# Sheet2.net
KiCad netlist of a schematic drawn in Altium Designer
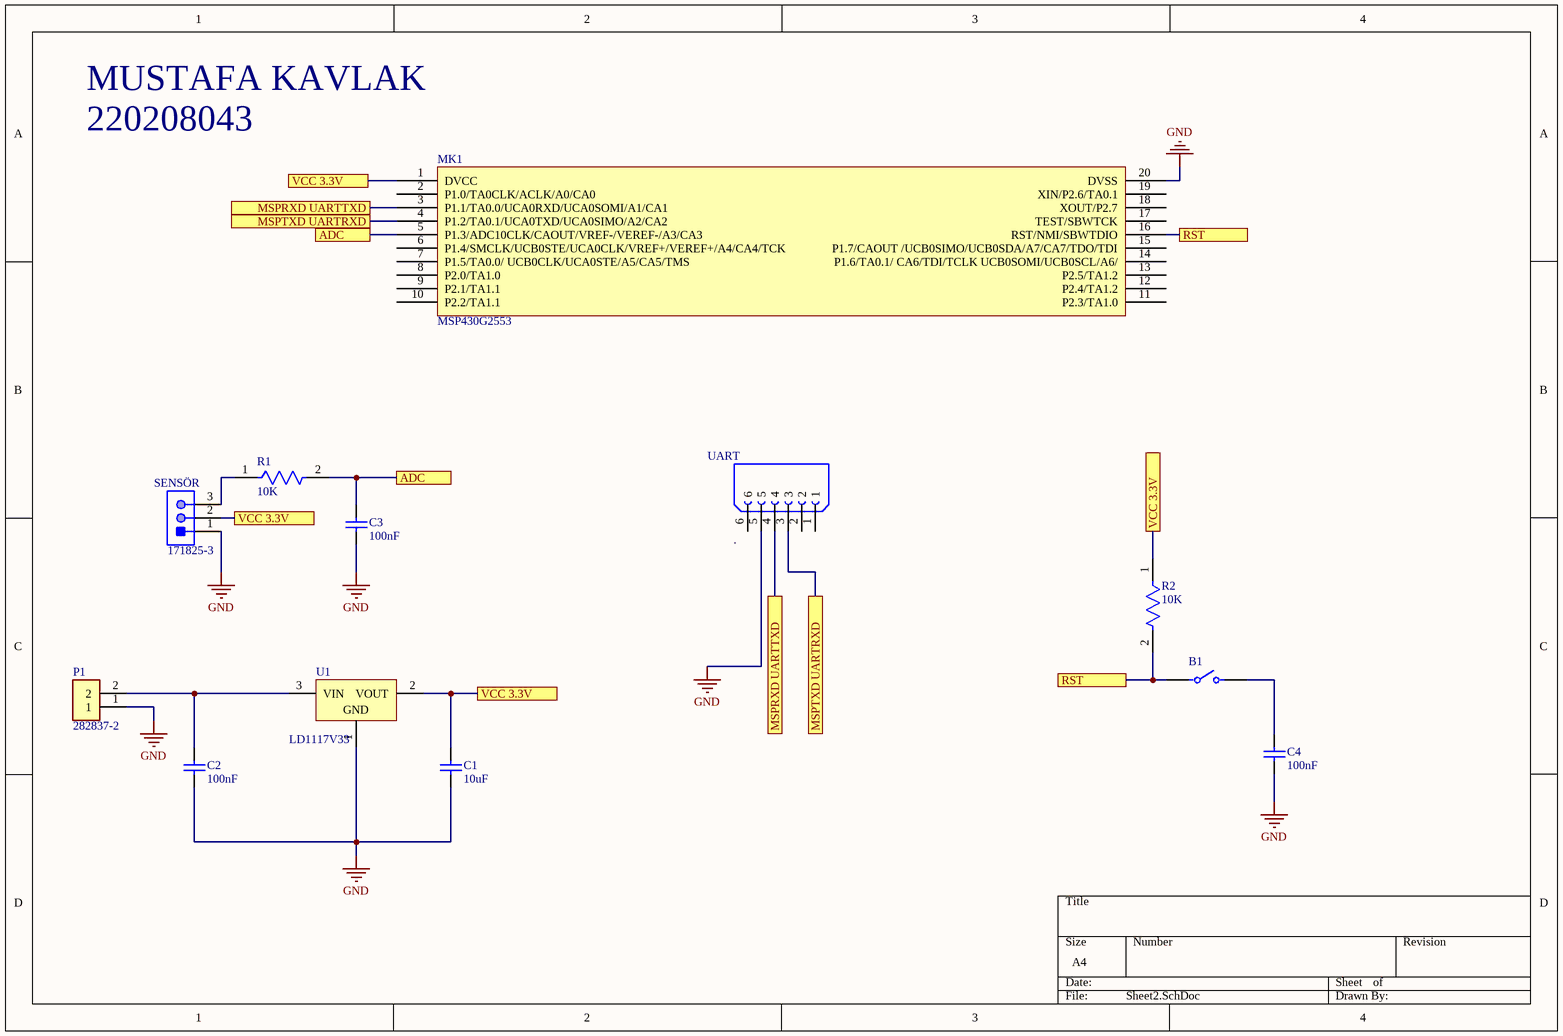
[diagram p0: Sheet2.SchDoc]

(export (version "E")
  (design (tool "Eeschema 10.0.6"))
  (components
    (comp (ref "B1")
      (value "1")
      (footprint "FP-147873-1-MFG")
      (description "SWITCH TACTILE SPST-NO 0.05A 24V")
      (fields
        (field (name "MANUFACTURER") "TE Connectivity")
        (field (name "MANUFACTURER PART NUMBER") "147873-1")
      )
      (libsource (lib "Altium Content Vault") (part "bb27bde45df87f1f469753f287ef5ae"))
    )
    (comp (ref "C1")
      (value "10uF")
      (footprint "CAPC1210(3225)100_M")
      (description "CAP 10nF 250V ±5% 1210 (3225 Metric) Thickness 1mm SMD")
      (fields (field (name "TOLERANCE") "Â±5%"))
      (libsource (lib "Altium Content Vault") (part "CAP"))
    )
    (comp (ref "C2")
      (value "100nF")
      (footprint "CAPC1210(3225)100_M")
      (description "CAP 10nF 250V ±5% 1210 (3225 Metric) Thickness 1mm SMD")
      (fields (field (name "TOLERANCE") "Â±5%"))
      (libsource (lib "Altium Content Vault") (part "CAP"))
    )
    (comp (ref "C3")
      (value "100nF")
      (footprint "CAPC1210(3225)100_M")
      (description "CAP 10nF 250V ±5% 1210 (3225 Metric) Thickness 1mm SMD")
      (fields (field (name "TOLERANCE") "Â±5%"))
      (libsource (lib "Altium Content Vault") (part "CAP"))
    )
    (comp (ref "C4")
      (value "100nF")
      (footprint "CAPC1210(3225)100_M")
      (description "CAP 10nF 250V ±5% 1210 (3225 Metric) Thickness 1mm SMD")
      (fields (field (name "TOLERANCE") "Â±5%"))
      (libsource (lib "Altium Content Vault") (part "CAP"))
    )
    (comp (ref "MK1")
      (value "MSP430G2553")
      (footprint "DIP20")
      (libsource (lib "Integrated_Library1") (part "MSP430G2553"))
    )
    (comp (ref "P1")
      (value "282837-2")
      (footprint "TE_282837-2")
      (fields (field (name "MF") "TE Connectivity"))
      (libsource (lib "282837-2") (part "282837-2"))
    )
    (comp (ref "R1")
      (value "10K")
      (footprint "FP-CRCW2512-e3-IPC_A")
      (description "RES Thick Film, 10kΩ, 5%, 1W, 200ppm/°C, 2512")
      (fields (field (name "TOLERANCE") "5%"))
      (libsource (lib "Altium Content Vault") (part "1029c3af85768c4190bb7ad29bc67b5"))
    )
    (comp (ref "R2")
      (value "10K")
      (footprint "FP-CRCW2512-e3-IPC_A")
      (description "RES Thick Film, 10kΩ, 5%, 1W, 200ppm/°C, 2512")
      (fields (field (name "TOLERANCE") "5%"))
      (libsource (lib "Altium Content Vault") (part "1029c3af85768c4190bb7ad29bc67b5"))
    )
    (comp (ref "SENSÖR")
      (value "171825-3")
      (footprint "TECO-171825-3_V")
      (fields (field (name "MANUFACTURER") "TE Connectivity"))
      (libsource (lib "Altium Content Vault") (part "CN-1P-M-R3"))
    )
    (comp (ref "U1")
      (value "LD1117V33")
      (footprint "TO220")
      (description "Fixed Low Drop Positive Voltage Regulator, 3.3V, 3-Pin TO-220")
      (libsource (lib "Altium Content Vault") (part "PM-REG-LD1117V-SIL3"))
    )
    (comp (ref "UART")
      (value ".")
      (footprint "PPTC061LFBNRC:SULLINS_PPTC061LFBN-RC")
      (fields
        (field (name "MF") "{'manufacturer': u'Sullins Connector Solutions'}")
        (field (name "MP") "PPTC061LFBN-RC")
      )
      (libsource (lib "*") (part "PPTC061LFBN-RC"))
    )
  )
  (nets
    (net (code "1") (name "/ADC") (class "Default")
      (node (ref "C3") (pin "2") (pinfunction "2_2") (pintype "passive"))
      (node (ref "MK1") (pin "5") (pinfunction "P1.3/ADC10CLK/CAOUT/VREF-/VEREF-/A3/CA3_5") (pintype "passive"))
      (node (ref "R1") (pin "2") (pinfunction "2_2") (pintype "passive"))
    )
    (net (code "2") (name "/MSPRXD UARTTXD") (class "Default")
      (node (ref "MK1") (pin "3") (pinfunction "P1.1/TA0.0/UCA0RXD/UCA0SOMI/A1/CA1_3") (pintype "passive"))
      (node (ref "UART") (pin "4") (pinfunction "4_4") (pintype "passive"))
    )
    (net (code "3") (name "/MSPTXD UARTRXD") (class "Default")
      (node (ref "MK1") (pin "4") (pinfunction "P1.2/TA0.1/UCA0TXD/UCA0SIMO/A2/CA2_4") (pintype "passive"))
      (node (ref "UART") (pin "3") (pinfunction "3_3") (pintype "passive"))
    )
    (net (code "4") (name "/RST") (class "Default")
      (node (ref "B1") (pin "1") (pinfunction "1_1") (pintype "passive"))
      (node (ref "MK1") (pin "16") (pinfunction "RST/NMI/SBWTDIO_16") (pintype "passive"))
      (node (ref "R2") (pin "2") (pinfunction "2_2") (pintype "passive"))
    )
    (net (code "5") (name "/VCC 3.3V") (class "Default")
      (node (ref "C1") (pin "2") (pinfunction "2_2") (pintype "passive"))
      (node (ref "MK1") (pin "1") (pinfunction "DVCC_1") (pintype "passive"))
      (node (ref "R2") (pin "1") (pinfunction "1_1") (pintype "passive"))
      (node (ref "SENSÖR") (pin "2") (pinfunction "2_2") (pintype "passive"))
      (node (ref "U1") (pin "2") (pinfunction "VOUT_2") (pintype "power_in"))
    )
    (net (code "6") (name "GND") (class "Default")
      (node (ref "C1") (pin "1") (pinfunction "1_1") (pintype "passive"))
      (node (ref "C2") (pin "1") (pinfunction "1_1") (pintype "passive"))
      (node (ref "C3") (pin "1") (pinfunction "1_1") (pintype "passive"))
      (node (ref "C4") (pin "1") (pinfunction "1_1") (pintype "passive"))
      (node (ref "MK1") (pin "20") (pinfunction "DVSS_20") (pintype "passive"))
      (node (ref "P1") (pin "1") (pinfunction "1_1") (pintype "passive"))
      (node (ref "SENSÖR") (pin "1") (pinfunction "1_1") (pintype "passive"))
      (node (ref "U1") (pin "1") (pinfunction "GND_1") (pintype "power_in"))
      (node (ref "UART") (pin "5") (pinfunction "5_5") (pintype "passive"))
    )
    (net (code "7") (name "Net-(B1-Pad2)") (class "Default")
      (node (ref "B1") (pin "2") (pinfunction "2_2") (pintype "passive"))
      (node (ref "C4") (pin "2") (pinfunction "2_2") (pintype "passive"))
    )
    (net (code "8") (name "Net-(R1-Pad1)") (class "Default")
      (node (ref "R1") (pin "1") (pinfunction "1_1") (pintype "passive"))
      (node (ref "SENSÖR") (pin "3") (pinfunction "3_3") (pintype "passive"))
    )
    (net (code "9") (name "Net-(U1-VIN)") (class "Default")
      (node (ref "C2") (pin "2") (pinfunction "2_2") (pintype "passive"))
      (node (ref "P1") (pin "2") (pinfunction "2_2") (pintype "passive"))
      (node (ref "U1") (pin "3") (pinfunction "VIN_3") (pintype "power_in"))
    )
    (net (code "10") (name "unconnected-(MK1-P1.0{slash}TA0CLK{slash}ACLK{slash}A0{slash}CA0-Pad2)") (class "Default")
      (node (ref "MK1") (pin "2") (pinfunction "P1.0/TA0CLK/ACLK/A0/CA0_2") (pintype "passive"))
    )
    (net (code "11") (name "unconnected-(MK1-P1.4{slash}SMCLK{slash}UCB0STE{slash}UCA0CLK{slash}VREF+{slash}VEREF+{slash}A4{slash}CA4{slash}TCK-Pad6)") (class "Default")
      (node (ref "MK1") (pin "6") (pinfunction "P1.4/SMCLK/UCB0STE/UCA0CLK/VREF+/VEREF+/A4/CA4/TCK_6") (pintype "passive"))
    )
    (net (code "12") (name "unconnected-(MK1-P1.5{slash}TA0.0{slash}_UCB0CLK{slash}UCA0STE{slash}A5{slash}CA5{slash}TMS-Pad7)") (class "Default")
      (node (ref "MK1") (pin "7") (pinfunction "P1.5/TA0.0/_UCB0CLK/UCA0STE/A5/CA5/TMS_7") (pintype "passive"))
    )
    (net (code "13") (name "unconnected-(MK1-P1.6{slash}TA0.1{slash}_CA6{slash}TDI{slash}TCLK_UCB0SOMI{slash}UCB0SCL{slash}A6{slash}-Pad14)") (class "Default")
      (node (ref "MK1") (pin "14") (pinfunction "P1.6/TA0.1/_CA6/TDI/TCLK_UCB0SOMI/UCB0SCL/A6/_14") (pintype "passive"))
    )
    (net (code "14") (name "unconnected-(MK1-P1.7{slash}CAOUT_{slash}UCB0SIMO{slash}UCB0SDA{slash}A7{slash}CA7{slash}TDO{slash}TDI-Pad15)") (class "Default")
      (node (ref "MK1") (pin "15") (pinfunction "P1.7/CAOUT_/UCB0SIMO/UCB0SDA/A7/CA7/TDO/TDI_15") (pintype "passive"))
    )
    (net (code "15") (name "unconnected-(MK1-P2.0{slash}TA1.0-Pad8)") (class "Default")
      (node (ref "MK1") (pin "8") (pinfunction "P2.0/TA1.0_8") (pintype "passive"))
    )
    (net (code "16") (name "unconnected-(MK1-P2.1{slash}TA1.1-Pad9)") (class "Default")
      (node (ref "MK1") (pin "9") (pinfunction "P2.1/TA1.1_9") (pintype "passive"))
    )
    (net (code "17") (name "unconnected-(MK1-P2.2{slash}TA1.1-Pad10)") (class "Default")
      (node (ref "MK1") (pin "10") (pinfunction "P2.2/TA1.1_10") (pintype "passive"))
    )
    (net (code "18") (name "unconnected-(MK1-P2.3{slash}TA1.0-Pad11)") (class "Default")
      (node (ref "MK1") (pin "11") (pinfunction "P2.3/TA1.0_11") (pintype "passive"))
    )
    (net (code "19") (name "unconnected-(MK1-P2.4{slash}TA1.2-Pad12)") (class "Default")
      (node (ref "MK1") (pin "12") (pinfunction "P2.4/TA1.2_12") (pintype "passive"))
    )
    (net (code "20") (name "unconnected-(MK1-P2.5{slash}TA1.2-Pad13)") (class "Default")
      (node (ref "MK1") (pin "13") (pinfunction "P2.5/TA1.2_13") (pintype "passive"))
    )
    (net (code "21") (name "unconnected-(MK1-TEST{slash}SBWTCK-Pad17)") (class "Default")
      (node (ref "MK1") (pin "17") (pinfunction "TEST/SBWTCK_17") (pintype "passive"))
    )
    (net (code "22") (name "unconnected-(MK1-XIN{slash}P2.6{slash}TA0.1-Pad19)") (class "Default")
      (node (ref "MK1") (pin "19") (pinfunction "XIN/P2.6/TA0.1_19") (pintype "passive"))
    )
    (net (code "23") (name "unconnected-(MK1-XOUT{slash}P2.7-Pad18)") (class "Default")
      (node (ref "MK1") (pin "18") (pinfunction "XOUT/P2.7_18") (pintype "passive"))
    )
    (net (code "24") (name "unconnected-(UART-Pad1)") (class "Default")
      (node (ref "UART") (pin "1") (pinfunction "1_1") (pintype "passive"))
    )
    (net (code "25") (name "unconnected-(UART-Pad2)") (class "Default")
      (node (ref "UART") (pin "2") (pinfunction "2_2") (pintype "passive"))
    )
    (net (code "26") (name "unconnected-(UART-Pad6)") (class "Default")
      (node (ref "UART") (pin "6") (pinfunction "6_6") (pintype "passive"))
    )
  )
)
